# I-Ching_Connection_Board_EasyEDA.net
KiCad netlist of a schematic drawn in EasyEDA
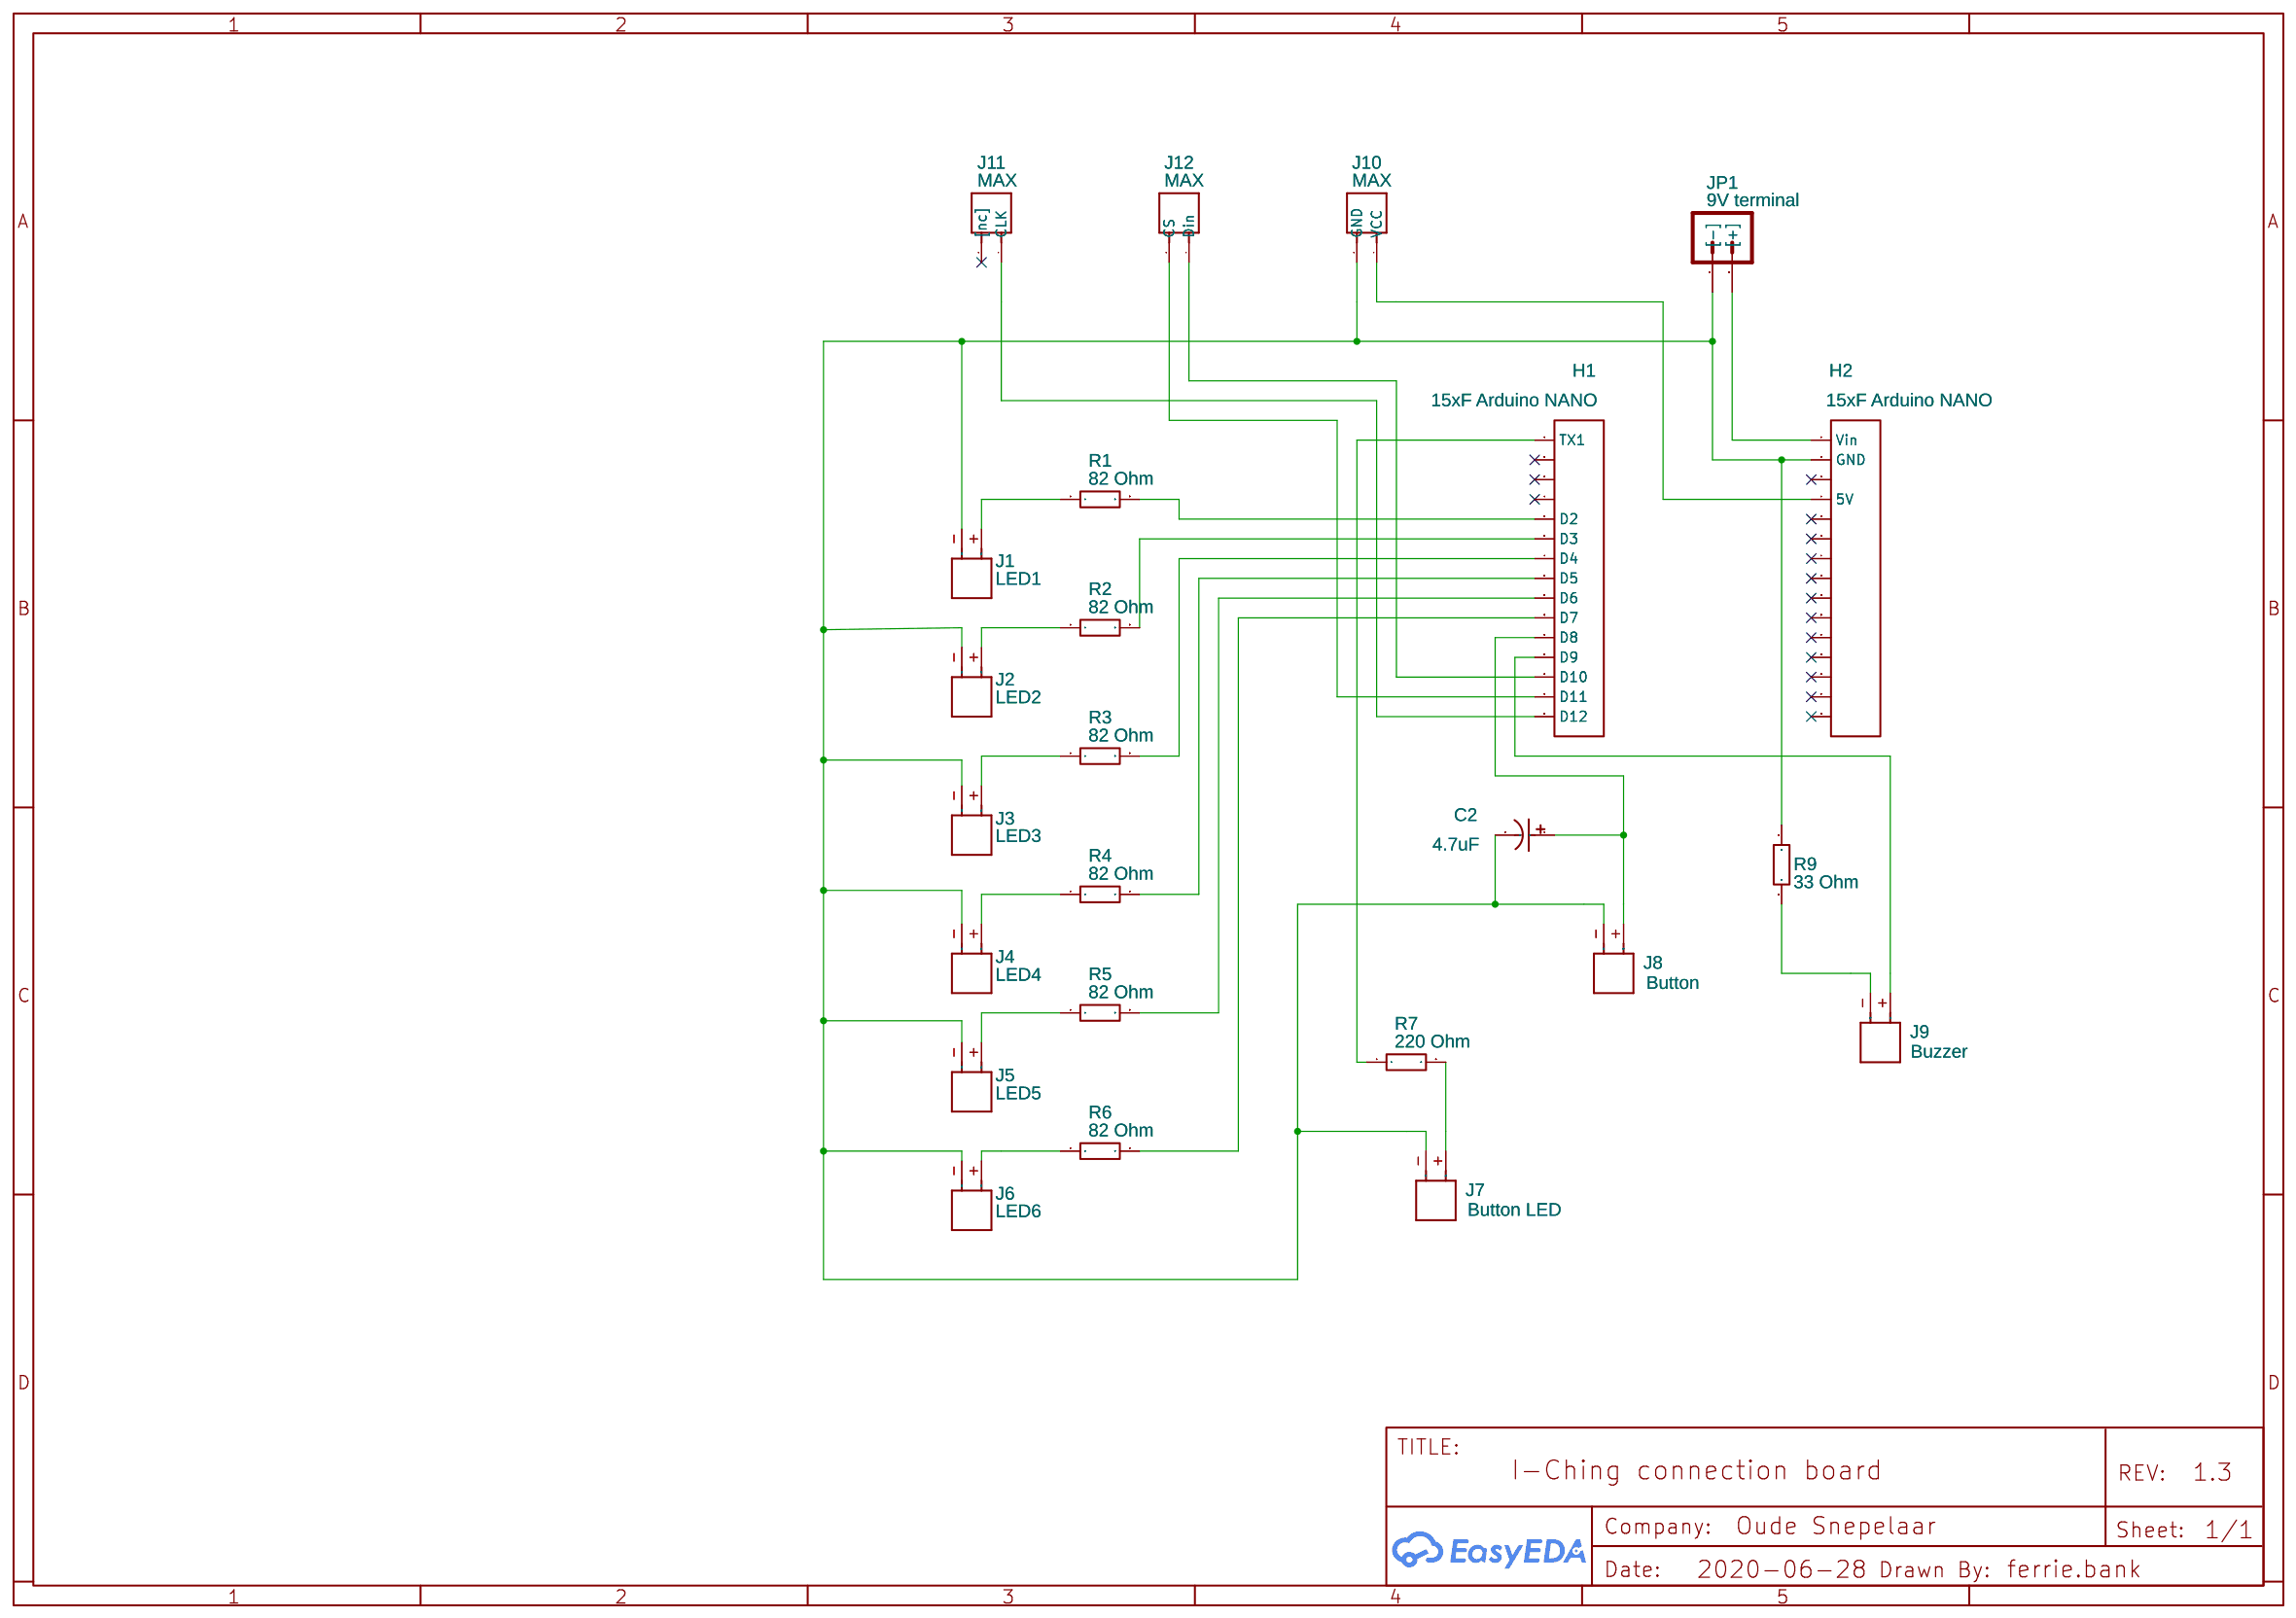
[diagram p0: schematic sheet]

(export (version "E")
  (design (tool "Eeschema 10.0.6"))
  (components
    (comp (ref "C2")
      (value "4.7uF")
      (fields (field (name "BOM_Manufacturer Part") "0.1UF 50V") (field (name "BOM_Supplier Part") "C28061"))
      (libsource (lib "") (part "0.1UF 50V"))
    )
    (comp (ref "H1")
      (value "15xF Arduino NANO")
      (fields
        (field (name "BOM_Manufacturer Part") "220S-1*15P H=8.5MM Ytype Gold-plated")
        (field (name "BOM_Supplier Part") "C124408")
      )
      (libsource (lib "") (part "Header-Female-2.54_1x15_1"))
    )
    (comp (ref "H2")
      (value "15xF Arduino NANO")
      (fields
        (field (name "BOM_Manufacturer Part") "220S-1*15P H=8.5MM Ytype Gold-plated")
        (field (name "BOM_Supplier Part") "C124408")
      )
      (libsource (lib "") (part "Header-Female-2.54_1x15"))
    )
    (comp (ref "J1")
      (value "LED1")
      (fields (field (name "BOM_Manufacturer Part") "ZB2001-02"))
      (libsource (lib "") (part "ZB2001-02"))
    )
    (comp (ref "J2")
      (value "LED2")
      (fields (field (name "BOM_Manufacturer Part") "ZB2001-02"))
      (libsource (lib "") (part "ZB2001-02"))
    )
    (comp (ref "J3")
      (value "LED3")
      (fields (field (name "BOM_Manufacturer Part") "ZB2001-02"))
      (libsource (lib "") (part "ZB2001-02"))
    )
    (comp (ref "J4")
      (value "LED4")
      (fields (field (name "BOM_Manufacturer Part") "ZB2001-02"))
      (libsource (lib "") (part "ZB2001-02"))
    )
    (comp (ref "J5")
      (value "LED5")
      (fields (field (name "BOM_Manufacturer Part") "ZB2001-02"))
      (libsource (lib "") (part "ZB2001-02"))
    )
    (comp (ref "J6")
      (value "LED6")
      (fields (field (name "BOM_Manufacturer Part") "ZB2001-02"))
      (libsource (lib "") (part "ZB2001-02"))
    )
    (comp (ref "J7")
      (value "Button LED")
      (fields (field (name "BOM_Manufacturer Part") "ZB2001-02"))
      (libsource (lib "") (part "ZB2001-02"))
    )
    (comp (ref "J8")
      (value "Button")
      (fields (field (name "BOM_Manufacturer Part") "ZB2001-02"))
      (libsource (lib "") (part "ZB2001-02"))
    )
    (comp (ref "J9")
      (value "Buzzer")
      (fields (field (name "BOM_Manufacturer Part") "ZB2001-02"))
      (libsource (lib "") (part "ZB2001-02"))
    )
    (comp (ref "J10")
      (value "MAX")
      (fields (field (name "BOM_Manufacturer Part") "ZB2001-02"))
      (libsource (lib "") (part "ZB2001-02_1"))
    )
    (comp (ref "J11")
      (value "MAX")
      (fields (field (name "BOM_Manufacturer Part") "ZB2001-02"))
      (libsource (lib "") (part "ZB2001-02_2"))
    )
    (comp (ref "J12")
      (value "MAX")
      (fields (field (name "BOM_Manufacturer Part") "ZB2001-02"))
      (libsource (lib "") (part "ZB2001-02_3"))
    )
    (comp (ref "JP1") (value "9V terminal") (libsource (lib "") (part "Screw Terminal 2-Pin (5mm Pitch)")))
    (comp (ref "R1")
      (value "82 Ohm")
      (fields
        (field (name "BOM_Manufacturer Part") "MFR-25FTE52-300K")
        (field (name "BOM_Supplier Part") "C173001")
      )
      (libsource (lib "") (part "MFR-25FTE52-300K"))
    )
    (comp (ref "R2")
      (value "82 Ohm")
      (fields
        (field (name "BOM_Manufacturer Part") "MFR-25FTE52-300K")
        (field (name "BOM_Supplier Part") "C173001")
      )
      (libsource (lib "") (part "MFR-25FTE52-300K"))
    )
    (comp (ref "R3")
      (value "82 Ohm")
      (fields
        (field (name "BOM_Manufacturer Part") "MFR-25FTE52-300K")
        (field (name "BOM_Supplier Part") "C173001")
      )
      (libsource (lib "") (part "MFR-25FTE52-300K"))
    )
    (comp (ref "R4")
      (value "82 Ohm")
      (fields
        (field (name "BOM_Manufacturer Part") "MFR-25FTE52-300K")
        (field (name "BOM_Supplier Part") "C173001")
      )
      (libsource (lib "") (part "MFR-25FTE52-300K"))
    )
    (comp (ref "R5")
      (value "82 Ohm")
      (fields
        (field (name "BOM_Manufacturer Part") "MFR-25FTE52-300K")
        (field (name "BOM_Supplier Part") "C173001")
      )
      (libsource (lib "") (part "MFR-25FTE52-300K"))
    )
    (comp (ref "R6")
      (value "82 Ohm")
      (fields
        (field (name "BOM_Manufacturer Part") "MFR-25FTE52-300K")
        (field (name "BOM_Supplier Part") "C173001")
      )
      (libsource (lib "") (part "MFR-25FTE52-300K"))
    )
    (comp (ref "R7")
      (value "220 Ohm")
      (fields
        (field (name "BOM_Manufacturer Part") "MFR-25FTE52-300K")
        (field (name "BOM_Supplier Part") "C173001")
      )
      (libsource (lib "") (part "MFR-25FTE52-300K"))
    )
    (comp (ref "R9")
      (value "33 Ohm")
      (fields
        (field (name "BOM_Manufacturer Part") "MFR-25FTE52-300K")
        (field (name "BOM_Supplier Part") "C173001")
      )
      (libsource (lib "") (part "MFR-25FTE52-300K_1"))
    )
  )
  (nets
    (net (code "1") (name "Net-(H1-D2)") (class "Default")
      (node (ref "H1") (pin "5") (pinfunction "D2_5") (pintype "unspecified"))
      (node (ref "R1") (pin "2") (pinfunction "2_2") (pintype "unspecified"))
    )
    (net (code "2") (name "Net-(H1-D3)") (class "Default")
      (node (ref "H1") (pin "6") (pinfunction "D3_6") (pintype "unspecified"))
      (node (ref "R2") (pin "2") (pinfunction "2_2") (pintype "unspecified"))
    )
    (net (code "3") (name "Net-(H1-D4)") (class "Default")
      (node (ref "H1") (pin "7") (pinfunction "D4_7") (pintype "unspecified"))
      (node (ref "R3") (pin "2") (pinfunction "2_2") (pintype "unspecified"))
    )
    (net (code "4") (name "Net-(H1-D5)") (class "Default")
      (node (ref "H1") (pin "8") (pinfunction "D5_8") (pintype "unspecified"))
      (node (ref "R4") (pin "2") (pinfunction "2_2") (pintype "unspecified"))
    )
    (net (code "5") (name "Net-(H1-D6)") (class "Default")
      (node (ref "H1") (pin "9") (pinfunction "D6_9") (pintype "unspecified"))
      (node (ref "R5") (pin "2") (pinfunction "2_2") (pintype "unspecified"))
    )
    (net (code "6") (name "Net-(H1-D7)") (class "Default")
      (node (ref "H1") (pin "10") (pinfunction "D7_10") (pintype "unspecified"))
      (node (ref "R6") (pin "2") (pinfunction "2_2") (pintype "unspecified"))
    )
    (net (code "7") (name "Net-(H1-D8)") (class "Default")
      (node (ref "C2") (pin "1") (pinfunction "1_1") (pintype "input"))
      (node (ref "H1") (pin "11") (pinfunction "D8_11") (pintype "unspecified"))
      (node (ref "J8") (pin "+") (pinfunction "P$1_+") (pintype "unspecified"))
    )
    (net (code "8") (name "Net-(H1-D9)") (class "Default")
      (node (ref "H1") (pin "12") (pinfunction "D9_12") (pintype "unspecified"))
      (node (ref "J9") (pin "+") (pinfunction "P$1_+") (pintype "unspecified"))
    )
    (net (code "9") (name "Net-(H1-D10)") (class "Default")
      (node (ref "H1") (pin "13") (pinfunction "D10_13") (pintype "unspecified"))
      (node (ref "J12") (pin "-") (pinfunction "Din_-") (pintype "unspecified"))
    )
    (net (code "10") (name "Net-(H1-D11)") (class "Default")
      (node (ref "H1") (pin "14") (pinfunction "D11_14") (pintype "unspecified"))
      (node (ref "J12") (pin "+") (pinfunction "CS_+") (pintype "unspecified"))
    )
    (net (code "11") (name "Net-(H1-D12)") (class "Default")
      (node (ref "H1") (pin "15") (pinfunction "D12_15") (pintype "unspecified"))
      (node (ref "J11") (pin "-") (pinfunction "CLK_-") (pintype "unspecified"))
    )
    (net (code "12") (name "Net-(H1-TX1)") (class "Default")
      (node (ref "H1") (pin "1") (pinfunction "TX1_1") (pintype "unspecified"))
      (node (ref "R7") (pin "1") (pinfunction "1_1") (pintype "unspecified"))
    )
    (net (code "13") (name "Net-(H2-5V)") (class "Default")
      (node (ref "H2") (pin "4") (pinfunction "5V_4") (pintype "unspecified"))
      (node (ref "J10") (pin "-") (pinfunction "VCC_-") (pintype "unspecified"))
    )
    (net (code "14") (name "Net-(H2-GND)") (class "Default")
      (node (ref "C2") (pin "2") (pinfunction "2_2") (pintype "input"))
      (node (ref "H2") (pin "2") (pinfunction "GND_2") (pintype "unspecified"))
      (node (ref "J1") (pin "-") (pinfunction "P$2_-") (pintype "unspecified"))
      (node (ref "J10") (pin "+") (pinfunction "GND_+") (pintype "unspecified"))
      (node (ref "J2") (pin "-") (pinfunction "P$2_-") (pintype "unspecified"))
      (node (ref "J3") (pin "-") (pinfunction "P$2_-") (pintype "unspecified"))
      (node (ref "J4") (pin "-") (pinfunction "P$2_-") (pintype "unspecified"))
      (node (ref "J5") (pin "-") (pinfunction "P$2_-") (pintype "unspecified"))
      (node (ref "J6") (pin "-") (pinfunction "P$2_-") (pintype "unspecified"))
      (node (ref "J7") (pin "-") (pinfunction "P$2_-") (pintype "unspecified"))
      (node (ref "J8") (pin "-") (pinfunction "P$2_-") (pintype "unspecified"))
      (node (ref "JP1") (pin "1") (pinfunction "[-]_1") (pintype "unspecified"))
      (node (ref "R9") (pin "1") (pinfunction "1_1") (pintype "unspecified"))
    )
    (net (code "15") (name "Net-(H2-Vin)") (class "Default")
      (node (ref "H2") (pin "1") (pinfunction "Vin_1") (pintype "unspecified"))
      (node (ref "JP1") (pin "2") (pinfunction "[+]_2") (pintype "unspecified"))
    )
    (net (code "16") (name "Net-(J1-P$1)") (class "Default")
      (node (ref "J1") (pin "+") (pinfunction "P$1_+") (pintype "unspecified"))
      (node (ref "R1") (pin "1") (pinfunction "1_1") (pintype "unspecified"))
    )
    (net (code "17") (name "Net-(J2-P$1)") (class "Default")
      (node (ref "J2") (pin "+") (pinfunction "P$1_+") (pintype "unspecified"))
      (node (ref "R2") (pin "1") (pinfunction "1_1") (pintype "unspecified"))
    )
    (net (code "18") (name "Net-(J3-P$1)") (class "Default")
      (node (ref "J3") (pin "+") (pinfunction "P$1_+") (pintype "unspecified"))
      (node (ref "R3") (pin "1") (pinfunction "1_1") (pintype "unspecified"))
    )
    (net (code "19") (name "Net-(J4-P$1)") (class "Default")
      (node (ref "J4") (pin "+") (pinfunction "P$1_+") (pintype "unspecified"))
      (node (ref "R4") (pin "1") (pinfunction "1_1") (pintype "unspecified"))
    )
    (net (code "20") (name "Net-(J5-P$1)") (class "Default")
      (node (ref "J5") (pin "+") (pinfunction "P$1_+") (pintype "unspecified"))
      (node (ref "R5") (pin "1") (pinfunction "1_1") (pintype "unspecified"))
    )
    (net (code "21") (name "Net-(J6-P$1)") (class "Default")
      (node (ref "J6") (pin "+") (pinfunction "P$1_+") (pintype "unspecified"))
      (node (ref "R6") (pin "1") (pinfunction "1_1") (pintype "unspecified"))
    )
    (net (code "22") (name "Net-(J7-P$1)") (class "Default")
      (node (ref "J7") (pin "+") (pinfunction "P$1_+") (pintype "unspecified"))
      (node (ref "R7") (pin "2") (pinfunction "2_2") (pintype "unspecified"))
    )
    (net (code "23") (name "Net-(J9-P$2)") (class "Default")
      (node (ref "J9") (pin "-") (pinfunction "P$2_-") (pintype "unspecified"))
      (node (ref "R9") (pin "2") (pinfunction "2_2") (pintype "unspecified"))
    )
    (net (code "24") (name "unconnected-(H1-Pad2)") (class "Default")
      (node (ref "H1") (pin "2") (pintype "unspecified+no_connect"))
    )
    (net (code "25") (name "unconnected-(H1-Pad3)") (class "Default")
      (node (ref "H1") (pin "3") (pintype "unspecified+no_connect"))
    )
    (net (code "26") (name "unconnected-(H1-Pad4)") (class "Default")
      (node (ref "H1") (pin "4") (pintype "unspecified+no_connect"))
    )
    (net (code "27") (name "unconnected-(H2-Pad3)") (class "Default")
      (node (ref "H2") (pin "3") (pintype "unspecified+no_connect"))
    )
    (net (code "28") (name "unconnected-(H2-Pad5)") (class "Default")
      (node (ref "H2") (pin "5") (pintype "unspecified+no_connect"))
    )
    (net (code "29") (name "unconnected-(H2-Pad6)") (class "Default")
      (node (ref "H2") (pin "6") (pintype "unspecified+no_connect"))
    )
    (net (code "30") (name "unconnected-(H2-Pad7)") (class "Default")
      (node (ref "H2") (pin "7") (pintype "unspecified+no_connect"))
    )
    (net (code "31") (name "unconnected-(H2-Pad8)") (class "Default")
      (node (ref "H2") (pin "8") (pintype "unspecified+no_connect"))
    )
    (net (code "32") (name "unconnected-(H2-Pad9)") (class "Default")
      (node (ref "H2") (pin "9") (pintype "unspecified+no_connect"))
    )
    (net (code "33") (name "unconnected-(H2-Pad10)") (class "Default")
      (node (ref "H2") (pin "10") (pintype "unspecified+no_connect"))
    )
    (net (code "34") (name "unconnected-(H2-Pad11)") (class "Default")
      (node (ref "H2") (pin "11") (pintype "unspecified+no_connect"))
    )
    (net (code "35") (name "unconnected-(H2-Pad12)") (class "Default")
      (node (ref "H2") (pin "12") (pintype "unspecified+no_connect"))
    )
    (net (code "36") (name "unconnected-(H2-Pad13)") (class "Default")
      (node (ref "H2") (pin "13") (pintype "unspecified+no_connect"))
    )
    (net (code "37") (name "unconnected-(H2-Pad14)") (class "Default")
      (node (ref "H2") (pin "14") (pintype "unspecified+no_connect"))
    )
    (net (code "38") (name "unconnected-(H2-Pad15)") (class "Default")
      (node (ref "H2") (pin "15") (pintype "unspecified+no_connect"))
    )
    (net (code "39") (name "unconnected-(J11-[nc]-Pad+)") (class "Default")
      (node (ref "J11") (pin "+") (pinfunction "[nc]_+") (pintype "unspecified+no_connect"))
    )
  )
)
